# bus.net
KiCad netlist of a schematic drawn in Altium Designer
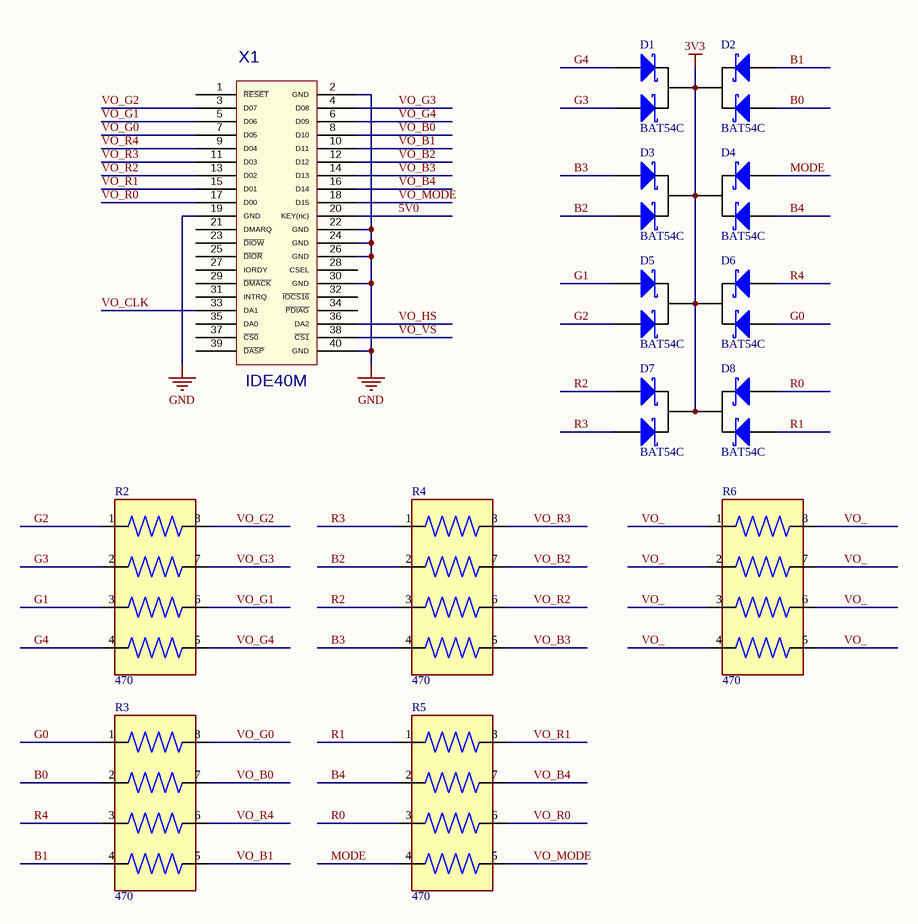
[diagram p0: bus.SchDoc]

(export (version "E")
  (design (tool "Eeschema 10.0.6"))
  (components
    (comp (ref "D1") (value "BAT54C") (footprint "SOT-23") (libsource (lib "Schlib") (part "BAT54C")))
    (comp (ref "D2") (value "BAT54C") (footprint "SOT-23") (libsource (lib "Schlib") (part "BAT54C")))
    (comp (ref "D3") (value "BAT54C") (footprint "SOT-23") (libsource (lib "Schlib") (part "BAT54C")))
    (comp (ref "D4") (value "BAT54C") (footprint "SOT-23") (libsource (lib "Schlib") (part "BAT54C")))
    (comp (ref "D5") (value "BAT54C") (footprint "SOT-23") (libsource (lib "Schlib") (part "BAT54C")))
    (comp (ref "D6") (value "BAT54C") (footprint "SOT-23") (libsource (lib "Schlib") (part "BAT54C")))
    (comp (ref "D7") (value "BAT54C") (footprint "SOT-23") (libsource (lib "Schlib") (part "BAT54C")))
    (comp (ref "D8") (value "BAT54C") (footprint "SOT-23") (libsource (lib "Schlib") (part "BAT54C")))
    (comp (ref "R2")
      (value "470")
      (footprint "RESCAV50P200X100X55-8N")
      (fields (field (name "MP") "CAT10-101J4LF"))
      (libsource (lib "Schlib") (part "CAT10-***4LF"))
    )
    (comp (ref "R3")
      (value "470")
      (footprint "RESCAV50P200X100X55-8N")
      (fields (field (name "MP") "CAT10-101J4LF"))
      (libsource (lib "Schlib") (part "CAT10-***4LF"))
    )
    (comp (ref "R4")
      (value "470")
      (footprint "RESCAV50P200X100X55-8N")
      (fields (field (name "MP") "CAT10-101J4LF"))
      (libsource (lib "Schlib") (part "CAT10-***4LF"))
    )
    (comp (ref "R5")
      (value "470")
      (footprint "RESCAV50P200X100X55-8N")
      (fields (field (name "MP") "CAT10-101J4LF"))
      (libsource (lib "Schlib") (part "CAT10-***4LF"))
    )
    (comp (ref "R6")
      (value "470")
      (footprint "RESCAV50P200X100X55-8N")
      (fields (field (name "MP") "CAT10-101J4LF"))
      (libsource (lib "Schlib") (part "CAT10-***4LF"))
    )
    (comp (ref "X1") (value "IDE40M") (footprint "IDE40M") (libsource (lib "Schlib") (part "IDE40M")))
  )
  (nets
    (net (code "1") (name "/5V0") (class "Default")
      (node (ref "X1") (pin "20") (pinfunction "KEY(nc)_20") (pintype "passive"))
    )
    (net (code "2") (name "/B0") (class "Default")
      (node (ref "D2") (pin "2") (pinfunction "A_2") (pintype "passive"))
      (node (ref "R3") (pin "2") (pinfunction "2_2") (pintype "passive"))
    )
    (net (code "3") (name "/B1") (class "Default")
      (node (ref "D2") (pin "1") (pinfunction "A_1") (pintype "passive"))
      (node (ref "R3") (pin "4") (pinfunction "4_4") (pintype "passive"))
    )
    (net (code "4") (name "/B2") (class "Default")
      (node (ref "D3") (pin "2") (pinfunction "A_2") (pintype "passive"))
      (node (ref "R4") (pin "2") (pinfunction "2_2") (pintype "passive"))
    )
    (net (code "5") (name "/B3") (class "Default")
      (node (ref "D3") (pin "1") (pinfunction "A_1") (pintype "passive"))
      (node (ref "R4") (pin "4") (pinfunction "4_4") (pintype "passive"))
    )
    (net (code "6") (name "/B4") (class "Default")
      (node (ref "D4") (pin "2") (pinfunction "A_2") (pintype "passive"))
      (node (ref "R5") (pin "2") (pinfunction "2_2") (pintype "passive"))
    )
    (net (code "7") (name "/G0") (class "Default")
      (node (ref "D6") (pin "2") (pinfunction "A_2") (pintype "passive"))
      (node (ref "R3") (pin "1") (pinfunction "1_1") (pintype "passive"))
    )
    (net (code "8") (name "/G1") (class "Default")
      (node (ref "D5") (pin "1") (pinfunction "A_1") (pintype "passive"))
      (node (ref "R2") (pin "3") (pinfunction "3_3") (pintype "passive"))
    )
    (net (code "9") (name "/G2") (class "Default")
      (node (ref "D5") (pin "2") (pinfunction "A_2") (pintype "passive"))
      (node (ref "R2") (pin "1") (pinfunction "1_1") (pintype "passive"))
    )
    (net (code "10") (name "/G3") (class "Default")
      (node (ref "D1") (pin "2") (pinfunction "A_2") (pintype "passive"))
      (node (ref "R2") (pin "2") (pinfunction "2_2") (pintype "passive"))
    )
    (net (code "11") (name "/G4") (class "Default")
      (node (ref "D1") (pin "1") (pinfunction "A_1") (pintype "passive"))
      (node (ref "R2") (pin "4") (pinfunction "4_4") (pintype "passive"))
    )
    (net (code "12") (name "/MODE") (class "Default")
      (node (ref "D4") (pin "1") (pinfunction "A_1") (pintype "passive"))
      (node (ref "R5") (pin "4") (pinfunction "4_4") (pintype "passive"))
    )
    (net (code "13") (name "/R0") (class "Default")
      (node (ref "D8") (pin "1") (pinfunction "A_1") (pintype "passive"))
      (node (ref "R5") (pin "3") (pinfunction "3_3") (pintype "passive"))
    )
    (net (code "14") (name "/R1") (class "Default")
      (node (ref "D8") (pin "2") (pinfunction "A_2") (pintype "passive"))
      (node (ref "R5") (pin "1") (pinfunction "1_1") (pintype "passive"))
    )
    (net (code "15") (name "/R2") (class "Default")
      (node (ref "D7") (pin "1") (pinfunction "A_1") (pintype "passive"))
      (node (ref "R4") (pin "3") (pinfunction "3_3") (pintype "passive"))
    )
    (net (code "16") (name "/R3") (class "Default")
      (node (ref "D7") (pin "2") (pinfunction "A_2") (pintype "passive"))
      (node (ref "R4") (pin "1") (pinfunction "1_1") (pintype "passive"))
    )
    (net (code "17") (name "/R4") (class "Default")
      (node (ref "D6") (pin "1") (pinfunction "A_1") (pintype "passive"))
      (node (ref "R3") (pin "3") (pinfunction "3_3") (pintype "passive"))
    )
    (net (code "18") (name "/VO_") (class "Default")
      (node (ref "R6") (pin "1") (pinfunction "1_1") (pintype "passive"))
      (node (ref "R6") (pin "2") (pinfunction "2_2") (pintype "passive"))
      (node (ref "R6") (pin "3") (pinfunction "3_3") (pintype "passive"))
      (node (ref "R6") (pin "4") (pinfunction "4_4") (pintype "passive"))
      (node (ref "R6") (pin "5") (pinfunction "5_5") (pintype "passive"))
      (node (ref "R6") (pin "6") (pinfunction "6_6") (pintype "passive"))
      (node (ref "R6") (pin "7") (pinfunction "7_7") (pintype "passive"))
      (node (ref "R6") (pin "8") (pinfunction "8_8") (pintype "passive"))
    )
    (net (code "19") (name "/VO_B0") (class "Default")
      (node (ref "R3") (pin "7") (pinfunction "7_7") (pintype "passive"))
      (node (ref "X1") (pin "8") (pinfunction "D10_8") (pintype "passive"))
    )
    (net (code "20") (name "/VO_B1") (class "Default")
      (node (ref "R3") (pin "5") (pinfunction "5_5") (pintype "passive"))
      (node (ref "X1") (pin "10") (pinfunction "D11_10") (pintype "passive"))
    )
    (net (code "21") (name "/VO_B2") (class "Default")
      (node (ref "R4") (pin "7") (pinfunction "7_7") (pintype "passive"))
      (node (ref "X1") (pin "12") (pinfunction "D12_12") (pintype "passive"))
    )
    (net (code "22") (name "/VO_B3") (class "Default")
      (node (ref "R4") (pin "5") (pinfunction "5_5") (pintype "passive"))
      (node (ref "X1") (pin "14") (pinfunction "D13_14") (pintype "passive"))
    )
    (net (code "23") (name "/VO_B4") (class "Default")
      (node (ref "R5") (pin "7") (pinfunction "7_7") (pintype "passive"))
      (node (ref "X1") (pin "16") (pinfunction "D14_16") (pintype "passive"))
    )
    (net (code "24") (name "/VO_CLK") (class "Default")
      (node (ref "X1") (pin "33") (pinfunction "DA1_33") (pintype "passive"))
    )
    (net (code "25") (name "/VO_G0") (class "Default")
      (node (ref "R3") (pin "8") (pinfunction "8_8") (pintype "passive"))
      (node (ref "X1") (pin "7") (pinfunction "D05_7") (pintype "passive"))
    )
    (net (code "26") (name "/VO_G1") (class "Default")
      (node (ref "R2") (pin "6") (pinfunction "6_6") (pintype "passive"))
      (node (ref "X1") (pin "5") (pinfunction "D06_5") (pintype "passive"))
    )
    (net (code "27") (name "/VO_G2") (class "Default")
      (node (ref "R2") (pin "8") (pinfunction "8_8") (pintype "passive"))
      (node (ref "X1") (pin "3") (pinfunction "D07_3") (pintype "passive"))
    )
    (net (code "28") (name "/VO_G3") (class "Default")
      (node (ref "R2") (pin "7") (pinfunction "7_7") (pintype "passive"))
      (node (ref "X1") (pin "4") (pinfunction "D08_4") (pintype "passive"))
    )
    (net (code "29") (name "/VO_G4") (class "Default")
      (node (ref "R2") (pin "5") (pinfunction "5_5") (pintype "passive"))
      (node (ref "X1") (pin "6") (pinfunction "D09_6") (pintype "passive"))
    )
    (net (code "30") (name "/VO_HS") (class "Default")
      (node (ref "X1") (pin "36") (pinfunction "DA2_36") (pintype "passive"))
    )
    (net (code "31") (name "/VO_MODE") (class "Default")
      (node (ref "R5") (pin "5") (pinfunction "5_5") (pintype "passive"))
      (node (ref "X1") (pin "18") (pinfunction "D15_18") (pintype "passive"))
    )
    (net (code "32") (name "/VO_R0") (class "Default")
      (node (ref "R5") (pin "6") (pinfunction "6_6") (pintype "passive"))
      (node (ref "X1") (pin "17") (pinfunction "D00_17") (pintype "passive"))
    )
    (net (code "33") (name "/VO_R1") (class "Default")
      (node (ref "R5") (pin "8") (pinfunction "8_8") (pintype "passive"))
      (node (ref "X1") (pin "15") (pinfunction "D01_15") (pintype "passive"))
    )
    (net (code "34") (name "/VO_R2") (class "Default")
      (node (ref "R4") (pin "6") (pinfunction "6_6") (pintype "passive"))
      (node (ref "X1") (pin "13") (pinfunction "D02_13") (pintype "passive"))
    )
    (net (code "35") (name "/VO_R3") (class "Default")
      (node (ref "R4") (pin "8") (pinfunction "8_8") (pintype "passive"))
      (node (ref "X1") (pin "11") (pinfunction "D03_11") (pintype "passive"))
    )
    (net (code "36") (name "/VO_R4") (class "Default")
      (node (ref "R3") (pin "6") (pinfunction "6_6") (pintype "passive"))
      (node (ref "X1") (pin "9") (pinfunction "D04_9") (pintype "passive"))
    )
    (net (code "37") (name "/VO_VS") (class "Default")
      (node (ref "X1") (pin "38") (pinfunction "~{CS1}_38") (pintype "passive"))
    )
    (net (code "38") (name "3V3") (class "Default")
      (node (ref "D1") (pin "3") (pinfunction "C_3") (pintype "passive"))
      (node (ref "D2") (pin "3") (pinfunction "C_3") (pintype "passive"))
      (node (ref "D3") (pin "3") (pinfunction "C_3") (pintype "passive"))
      (node (ref "D4") (pin "3") (pinfunction "C_3") (pintype "passive"))
      (node (ref "D5") (pin "3") (pinfunction "C_3") (pintype "passive"))
      (node (ref "D6") (pin "3") (pinfunction "C_3") (pintype "passive"))
      (node (ref "D7") (pin "3") (pinfunction "C_3") (pintype "passive"))
      (node (ref "D8") (pin "3") (pinfunction "C_3") (pintype "passive"))
    )
    (net (code "39") (name "GND") (class "Default")
      (node (ref "X1") (pin "19") (pinfunction "GND_19") (pintype "passive"))
      (node (ref "X1") (pin "2") (pinfunction "GND_2") (pintype "passive"))
      (node (ref "X1") (pin "22") (pinfunction "GND_22") (pintype "passive"))
      (node (ref "X1") (pin "24") (pinfunction "GND_24") (pintype "passive"))
      (node (ref "X1") (pin "26") (pinfunction "GND_26") (pintype "passive"))
      (node (ref "X1") (pin "30") (pinfunction "GND_30") (pintype "passive"))
      (node (ref "X1") (pin "40") (pinfunction "GND_40") (pintype "passive"))
    )
    (net (code "40") (name "unconnected-(X1-CSEL-Pad28)") (class "Default")
      (node (ref "X1") (pin "28") (pinfunction "CSEL_28") (pintype "passive"))
    )
    (net (code "41") (name "unconnected-(X1-DA0-Pad35)") (class "Default")
      (node (ref "X1") (pin "35") (pinfunction "DA0_35") (pintype "passive"))
    )
    (net (code "42") (name "unconnected-(X1-DMARQ-Pad21)") (class "Default")
      (node (ref "X1") (pin "21") (pinfunction "DMARQ_21") (pintype "passive"))
    )
    (net (code "43") (name "unconnected-(X1-INTRQ-Pad31)") (class "Default")
      (node (ref "X1") (pin "31") (pinfunction "INTRQ_31") (pintype "passive"))
    )
    (net (code "44") (name "unconnected-(X1-IORDY-Pad27)") (class "Default")
      (node (ref "X1") (pin "27") (pinfunction "IORDY_27") (pintype "passive"))
    )
    (net (code "45") (name "unconnected-(X1-~{CS0}-Pad37)") (class "Default")
      (node (ref "X1") (pin "37") (pinfunction "~{CS0}_37") (pintype "passive"))
    )
    (net (code "46") (name "unconnected-(X1-~{DASP}-Pad39)") (class "Default")
      (node (ref "X1") (pin "39") (pinfunction "~{DASP}_39") (pintype "passive"))
    )
    (net (code "47") (name "unconnected-(X1-~{DIOR}-Pad25)") (class "Default")
      (node (ref "X1") (pin "25") (pinfunction "~{DIOR}_25") (pintype "passive"))
    )
    (net (code "48") (name "unconnected-(X1-~{DIOW}-Pad23)") (class "Default")
      (node (ref "X1") (pin "23") (pinfunction "~{DIOW}_23") (pintype "passive"))
    )
    (net (code "49") (name "unconnected-(X1-~{DMACK}-Pad29)") (class "Default")
      (node (ref "X1") (pin "29") (pinfunction "~{DMACK}_29") (pintype "passive"))
    )
    (net (code "50") (name "unconnected-(X1-~{IOCS16}-Pad32)") (class "Default")
      (node (ref "X1") (pin "32") (pinfunction "~{IOCS16}_32") (pintype "passive"))
    )
    (net (code "51") (name "unconnected-(X1-~{PDIAG}-Pad34)") (class "Default")
      (node (ref "X1") (pin "34") (pinfunction "~{PDIAG}_34") (pintype "passive"))
    )
    (net (code "52") (name "unconnected-(X1-~{RESET}-Pad1)") (class "Default")
      (node (ref "X1") (pin "1") (pinfunction "~{RESET}_1") (pintype "passive"))
    )
  )
)
